# MT7601.net
KiCad netlist of a schematic drawn in Altium Designer
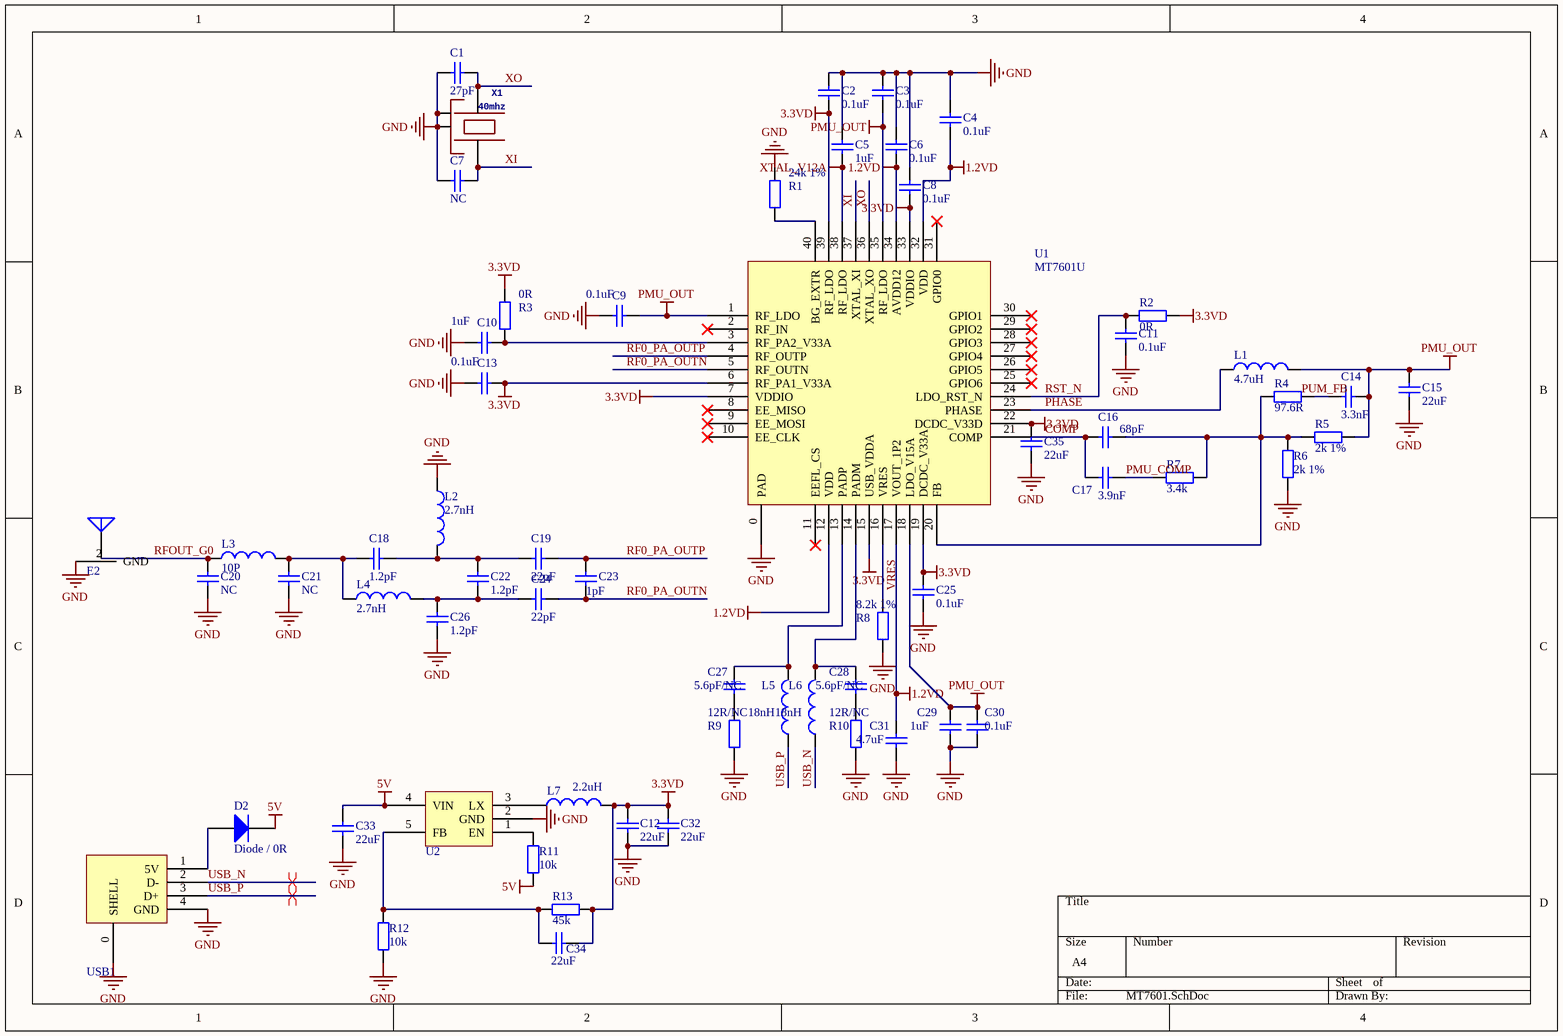
[diagram p0: MT7601.SchDoc]

(export (version "E")
  (design (tool "Eeschema 10.0.6"))
  (components
    (comp (ref "C1")
      (value "27pF")
      (footprint "0402")
      (description "Capacitor")
      (fields (field (name "PUBLISHER") "Altium Limited"))
      (libsource (lib "RTC6705") (part "Cap"))
    )
    (comp (ref "C2")
      (value "0.1uF")
      (footprint "0402")
      (description "Capacitor")
      (fields (field (name "PUBLISHER") "Altium Limited"))
      (libsource (lib "RTC6705") (part "Cap"))
    )
    (comp (ref "C3")
      (value "0.1uF")
      (footprint "0402")
      (description "Capacitor")
      (fields (field (name "PUBLISHER") "Altium Limited"))
      (libsource (lib "RTC6705") (part "Cap"))
    )
    (comp (ref "C4")
      (value "0.1uF")
      (footprint "0402")
      (description "Capacitor")
      (fields (field (name "PUBLISHER") "Altium Limited"))
      (libsource (lib "RTC6705") (part "Cap"))
    )
    (comp (ref "C5")
      (value "1uF")
      (footprint "0402")
      (description "Capacitor")
      (fields (field (name "PUBLISHER") "Altium Limited"))
      (libsource (lib "RTC6705") (part "Cap"))
    )
    (comp (ref "C6")
      (value "0.1uF")
      (footprint "0402")
      (description "Capacitor")
      (fields (field (name "PUBLISHER") "Altium Limited"))
      (libsource (lib "RTC6705") (part "Cap"))
    )
    (comp (ref "C7")
      (value "NC")
      (footprint "0402")
      (description "Capacitor")
      (fields (field (name "PUBLISHER") "Altium Limited"))
      (libsource (lib "RTC6705") (part "Cap"))
    )
    (comp (ref "C8")
      (value "0.1uF")
      (footprint "0402")
      (description "Capacitor")
      (fields (field (name "PUBLISHER") "Altium Limited"))
      (libsource (lib "RTC6705") (part "Cap"))
    )
    (comp (ref "C9")
      (value "0.1uF")
      (footprint "0402")
      (description "Capacitor")
      (fields (field (name "PUBLISHER") "Altium Limited"))
      (libsource (lib "RTC6705") (part "Cap"))
    )
    (comp (ref "C10")
      (value "1uF")
      (footprint "0402")
      (description "Capacitor")
      (fields (field (name "PUBLISHER") "Altium Limited"))
      (libsource (lib "RTC6705") (part "Cap"))
    )
    (comp (ref "C11")
      (value "0.1uF")
      (footprint "0402")
      (description "Capacitor")
      (fields (field (name "PUBLISHER") "Altium Limited"))
      (libsource (lib "RTC6705") (part "Cap"))
    )
    (comp (ref "C12")
      (value "22uF")
      (footprint "0805")
      (description "Capacitor")
      (fields (field (name "Comment") "Cap") (field (name "PUBLISHER") "Altium Limited"))
      (libsource (lib "RTC6705") (part "Cap"))
    )
    (comp (ref "C13")
      (value "0.1uF")
      (footprint "0402")
      (description "Capacitor")
      (fields (field (name "PUBLISHER") "Altium Limited"))
      (libsource (lib "RTC6705") (part "Cap"))
    )
    (comp (ref "C14")
      (value "3.3nF")
      (footprint "0402")
      (description "Capacitor")
      (fields (field (name "PUBLISHER") "Altium Limited"))
      (libsource (lib "RTC6705") (part "Cap"))
    )
    (comp (ref "C15")
      (value "22uF")
      (footprint "0805")
      (description "Capacitor")
      (fields (field (name "Comment") "Cap") (field (name "PUBLISHER") "Altium Limited"))
      (libsource (lib "RTC6705") (part "Cap"))
    )
    (comp (ref "C16")
      (value "68pF")
      (footprint "0402")
      (description "Capacitor")
      (fields (field (name "PUBLISHER") "Altium Limited"))
      (libsource (lib "RTC6705") (part "Cap"))
    )
    (comp (ref "C17")
      (value "3.9nF")
      (footprint "0402")
      (description "Capacitor")
      (fields (field (name "PUBLISHER") "Altium Limited"))
      (libsource (lib "RTC6705") (part "Cap"))
    )
    (comp (ref "C18")
      (value "1.2pF")
      (footprint "0402")
      (description "Capacitor")
      (fields (field (name "PUBLISHER") "Altium Limited"))
      (libsource (lib "RTC6705") (part "Cap"))
    )
    (comp (ref "C19")
      (value "22pF")
      (footprint "0402")
      (description "Capacitor")
      (fields (field (name "PUBLISHER") "Altium Limited"))
      (libsource (lib "RTC6705") (part "Cap"))
    )
    (comp (ref "C20")
      (value "NC")
      (footprint "0402")
      (description "Capacitor")
      (fields (field (name "PUBLISHER") "Altium Limited"))
      (libsource (lib "RTC6705") (part "Cap"))
    )
    (comp (ref "C21")
      (value "NC")
      (footprint "0402")
      (description "Capacitor")
      (fields (field (name "PUBLISHER") "Altium Limited"))
      (libsource (lib "RTC6705") (part "Cap"))
    )
    (comp (ref "C22")
      (value "1.2pF")
      (footprint "0402")
      (description "Capacitor")
      (fields (field (name "PUBLISHER") "Altium Limited"))
      (libsource (lib "RTC6705") (part "Cap"))
    )
    (comp (ref "C23")
      (value "1pF")
      (footprint "0402")
      (description "Capacitor")
      (fields (field (name "PUBLISHER") "Altium Limited"))
      (libsource (lib "RTC6705") (part "Cap"))
    )
    (comp (ref "C24")
      (value "22pF")
      (footprint "0402")
      (description "Capacitor")
      (fields (field (name "PUBLISHER") "Altium Limited"))
      (libsource (lib "RTC6705") (part "Cap"))
    )
    (comp (ref "C25")
      (value "0.1uF")
      (footprint "0402")
      (description "Capacitor")
      (fields (field (name "PUBLISHER") "Altium Limited"))
      (libsource (lib "RTC6705") (part "Cap"))
    )
    (comp (ref "C26")
      (value "1.2pF")
      (footprint "0402")
      (description "Capacitor")
      (fields (field (name "PUBLISHER") "Altium Limited"))
      (libsource (lib "RTC6705") (part "Cap"))
    )
    (comp (ref "C27")
      (value "5.6pF/NC")
      (footprint "0402")
      (description "Capacitor")
      (fields (field (name "PUBLISHER") "Altium Limited"))
      (libsource (lib "RTC6705") (part "Cap"))
    )
    (comp (ref "C28")
      (value "5.6pF/NC")
      (footprint "0402")
      (description "Capacitor")
      (fields (field (name "PUBLISHER") "Altium Limited"))
      (libsource (lib "RTC6705") (part "Cap"))
    )
    (comp (ref "C29")
      (value "1uF")
      (footprint "0402")
      (description "Capacitor")
      (fields (field (name "PUBLISHER") "Altium Limited"))
      (libsource (lib "RTC6705") (part "Cap"))
    )
    (comp (ref "C30")
      (value "0.1uF")
      (footprint "0402")
      (description "Capacitor")
      (fields (field (name "PUBLISHER") "Altium Limited"))
      (libsource (lib "RTC6705") (part "Cap"))
    )
    (comp (ref "C31")
      (value "4.7uF")
      (footprint "0603")
      (description "Capacitor")
      (fields (field (name "PUBLISHER") "Altium Limited"))
      (libsource (lib "RTC6705") (part "Cap"))
    )
    (comp (ref "C32")
      (value "22uF")
      (footprint "0805")
      (description "Capacitor")
      (fields (field (name "Comment") "Cap") (field (name "PUBLISHER") "Altium Limited"))
      (libsource (lib "RTC6705") (part "Cap"))
    )
    (comp (ref "C33")
      (value "22uF")
      (footprint "0805")
      (description "Capacitor")
      (fields (field (name "Comment") "Cap") (field (name "PUBLISHER") "Altium Limited"))
      (libsource (lib "RTC6705") (part "Cap"))
    )
    (comp (ref "C34")
      (value "22uF")
      (footprint "0402")
      (description "Capacitor")
      (fields (field (name "Comment") "Cap") (field (name "PUBLISHER") "Altium Limited"))
      (libsource (lib "RTC6705") (part "Cap"))
    )
    (comp (ref "C35")
      (value "22uF")
      (footprint "0805")
      (description "Capacitor")
      (fields (field (name "Comment") "Cap") (field (name "PUBLISHER") "Altium Limited"))
      (libsource (lib "RTC6705") (part "Cap"))
    )
    (comp (ref "D2")
      (value "Diode / 0R")
      (footprint "0805")
      (description "Default Diode")
      (fields (field (name "PUBLISHER") "Altium Limited"))
      (libsource (lib "Miscellaneous Devices") (part "Diode"))
    )
    (comp (ref "E2")
      (value "Antenna")
      (footprint "IPEX")
      (description "Generic Antenna")
      (fields (field (name "PUBLISHER") "Altium Limited"))
      (libsource (lib "Miscellaneous Devices") (part "Antenna"))
    )
    (comp (ref "L1")
      (value "4.7uH")
      (footprint "0805")
      (description "Inductor")
      (fields (field (name "PUBLISHER") "Altium Limited"))
      (libsource (lib "Miscellaneous Devices") (part "Inductor"))
    )
    (comp (ref "L2")
      (value "2.7nH")
      (footprint "0402")
      (description "Inductor")
      (fields (field (name "PUBLISHER") "Altium Limited"))
      (libsource (lib "Miscellaneous Devices") (part "Inductor"))
    )
    (comp (ref "L3")
      (value "10P")
      (footprint "0402")
      (description "Inductor")
      (fields (field (name "PUBLISHER") "Altium Limited"))
      (libsource (lib "Miscellaneous Devices") (part "Inductor"))
    )
    (comp (ref "L4")
      (value "2.7nH")
      (footprint "0402")
      (description "Inductor")
      (fields (field (name "PUBLISHER") "Altium Limited"))
      (libsource (lib "Miscellaneous Devices") (part "Inductor"))
    )
    (comp (ref "L5")
      (value "18nH")
      (footprint "0402")
      (description "Inductor")
      (fields (field (name "PUBLISHER") "Altium Limited"))
      (libsource (lib "Miscellaneous Devices") (part "Inductor"))
    )
    (comp (ref "L6")
      (value "18nH")
      (footprint "0402")
      (description "Inductor")
      (fields (field (name "PUBLISHER") "Altium Limited"))
      (libsource (lib "Miscellaneous Devices") (part "Inductor"))
    )
    (comp (ref "L7")
      (value "2.2uH")
      (footprint "0805")
      (description "Inductor")
      (fields (field (name "PUBLISHER") "Altium Limited"))
      (libsource (lib "Miscellaneous Devices") (part "Inductor"))
    )
    (comp (ref "R1")
      (value "24k 1%")
      (footprint "0402")
      (description "Resistor")
      (fields (field (name "PUBLISHER") "Altium Limited"))
      (libsource (lib "RTC6705") (part "Res2"))
    )
    (comp (ref "R2")
      (value "0R")
      (footprint "0402")
      (description "Resistor")
      (fields (field (name "PUBLISHER") "Altium Limited"))
      (libsource (lib "") (part "Res2_2"))
    )
    (comp (ref "R3")
      (value "0R")
      (footprint "0402")
      (description "Resistor")
      (fields (field (name "PUBLISHER") "Altium Limited"))
      (libsource (lib "RTC6705") (part "Res2"))
    )
    (comp (ref "R4")
      (value "97.6R")
      (footprint "0402")
      (description "Resistor")
      (fields (field (name "PUBLISHER") "Altium Limited"))
      (libsource (lib "") (part "Res2_2"))
    )
    (comp (ref "R5")
      (value "2k 1%")
      (footprint "0402")
      (description "Resistor")
      (fields (field (name "PUBLISHER") "Altium Limited"))
      (libsource (lib "") (part "Res2_2"))
    )
    (comp (ref "R6")
      (value "2k 1%")
      (footprint "0402")
      (description "Resistor")
      (fields (field (name "PUBLISHER") "Altium Limited"))
      (libsource (lib "") (part "Res2_1"))
    )
    (comp (ref "R7")
      (value "3.4k")
      (footprint "0402")
      (description "Resistor")
      (fields (field (name "PUBLISHER") "Altium Limited"))
      (libsource (lib "") (part "Res2_2"))
    )
    (comp (ref "R8")
      (value "8.2k 1%")
      (footprint "0402")
      (description "Resistor")
      (fields (field (name "PUBLISHER") "Altium Limited"))
      (libsource (lib "RTC6705") (part "Res2"))
    )
    (comp (ref "R9")
      (value "12R/NC")
      (footprint "0402")
      (description "Resistor")
      (fields (field (name "PUBLISHER") "Altium Limited"))
      (libsource (lib "RTC6705") (part "Res2"))
    )
    (comp (ref "R10")
      (value "12R/NC")
      (footprint "0402")
      (description "Resistor")
      (fields (field (name "PUBLISHER") "Altium Limited"))
      (libsource (lib "RTC6705") (part "Res2"))
    )
    (comp (ref "R11")
      (value "10k")
      (footprint "0402")
      (description "Resistor")
      (fields (field (name "PUBLISHER") "Altium Limited"))
      (libsource (lib "") (part "Res2_1"))
    )
    (comp (ref "R12")
      (value "10k")
      (footprint "0402")
      (description "Resistor")
      (fields (field (name "PUBLISHER") "Altium Limited"))
      (libsource (lib "RTC6705") (part "Res2"))
    )
    (comp (ref "R13")
      (value "45k")
      (footprint "0402")
      (description "Resistor")
      (fields (field (name "PUBLISHER") "Altium Limited"))
      (libsource (lib "") (part "Res2_3"))
    )
    (comp (ref "U1") (value "MT7601U") (footprint "MT7601U") (libsource (lib "WifiGain") (part "MT7601U")))
    (comp (ref "U2") (value "RT8059") (footprint "SOT23-5") (libsource (lib "WifiGain") (part "RT8059")))
    (comp (ref "USB1") (value "USB-A") (footprint "USB-A-Male") (libsource (lib "WifiGain") (part "USB-A")))
    (comp (ref "X1")
      (value "40mhz")
      (footprint "OSCILLATOR-3.2X2.5")
      (description "Crystal Oscillator in 3.2x2.5 SMD")
      (libsource (lib "sch") (part "OSCILLATOR-3.2X2.5"))
    )
  )
  (nets
    (net (code "1") (name "/COMP") (class "Default")
      (node (ref "C16") (pin "2") (pinfunction "2_2") (pintype "passive"))
      (node (ref "C17") (pin "2") (pinfunction "2_2") (pintype "passive"))
      (node (ref "U1") (pin "21") (pinfunction "COMP_21") (pintype "passive"))
    )
    (net (code "2") (name "/PHASE") (class "Default")
      (node (ref "L1") (pin "1") (pinfunction "1_1") (pintype "passive"))
      (node (ref "U1") (pin "23") (pinfunction "PHASE_23") (pintype "passive"))
    )
    (net (code "3") (name "/PMU_COMP") (class "Default")
      (node (ref "C17") (pin "1") (pinfunction "1_1") (pintype "passive"))
      (node (ref "R7") (pin "2") (pinfunction "2_2") (pintype "passive"))
    )
    (net (code "5") (name "/RF0_PA_OUTN") (class "Default")
      (node (ref "C23") (pin "1") (pinfunction "1_1") (pintype "passive"))
      (node (ref "C24") (pin "2") (pinfunction "2_2") (pintype "passive"))
      (node (ref "U1") (pin "5") (pinfunction "RF_OUTN_5") (pintype "passive"))
    )
    (net (code "6") (name "/RF0_PA_OUTP") (class "Default")
      (node (ref "C19") (pin "2") (pinfunction "2_2") (pintype "passive"))
      (node (ref "C23") (pin "2") (pinfunction "2_2") (pintype "passive"))
      (node (ref "U1") (pin "4") (pinfunction "RF_OUTP_4") (pintype "passive"))
    )
    (net (code "7") (name "/RFOUT_G0") (class "Default")
      (node (ref "C20") (pin "2") (pinfunction "2_2") (pintype "passive"))
      (node (ref "E2") (pin "1") (pinfunction "ANT_1") (pintype "passive"))
      (node (ref "L3") (pin "1") (pinfunction "1_1") (pintype "passive"))
    )
    (net (code "8") (name "/RST_N") (class "Default")
      (node (ref "C11") (pin "1") (pinfunction "1_1") (pintype "passive"))
      (node (ref "R2") (pin "2") (pinfunction "2_2") (pintype "passive"))
      (node (ref "U1") (pin "24") (pinfunction "LDO_RST_N_24") (pintype "passive"))
    )
    (net (code "9") (name "/USB_N") (class "Default")
      (node (ref "L6") (pin "1") (pinfunction "1_1") (pintype "passive"))
      (node (ref "USB1") (pin "2") (pinfunction "D-_2") (pintype "passive"))
    )
    (net (code "10") (name "/USB_P") (class "Default")
      (node (ref "L5") (pin "1") (pinfunction "1_1") (pintype "passive"))
      (node (ref "USB1") (pin "3") (pinfunction "D+_3") (pintype "passive"))
    )
    (net (code "11") (name "/VRES") (class "Default")
      (node (ref "R8") (pin "2") (pinfunction "2_2") (pintype "passive"))
      (node (ref "U1") (pin "16") (pinfunction "VRES_16") (pintype "passive"))
    )
    (net (code "12") (name "/XI") (class "Default")
      (node (ref "C7") (pin "2") (pinfunction "2_2") (pintype "passive"))
      (node (ref "U1") (pin "37") (pinfunction "XTAL_XI_37") (pintype "passive"))
      (node (ref "X1") (pin "3") (pinfunction "3_3") (pintype "passive"))
    )
    (net (code "13") (name "/XO") (class "Default")
      (node (ref "C1") (pin "2") (pinfunction "2_2") (pintype "passive"))
      (node (ref "U1") (pin "36") (pinfunction "XTAL_XO_36") (pintype "passive"))
      (node (ref "X1") (pin "1") (pinfunction "1_1") (pintype "passive"))
    )
    (net (code "14") (name "1.2VD") (class "Default")
      (node (ref "C31") (pin "1") (pinfunction "1_1") (pintype "passive"))
      (node (ref "C4") (pin "2") (pinfunction "2_2") (pintype "passive"))
      (node (ref "C6") (pin "2") (pinfunction "2_2") (pintype "passive"))
      (node (ref "U1") (pin "12") (pinfunction "VDD_12") (pintype "passive"))
      (node (ref "U1") (pin "17") (pinfunction "VOUT_1P2_17") (pintype "passive"))
      (node (ref "U1") (pin "32") (pinfunction "VDD_32") (pintype "passive"))
      (node (ref "U1") (pin "34") (pinfunction "AVDD12_34") (pintype "passive"))
    )
    (net (code "15") (name "3.3VD") (class "Default")
      (node (ref "C12") (pin "2") (pinfunction "2_2") (pintype "passive"))
      (node (ref "C13") (pin "1") (pinfunction "1_1") (pintype "passive"))
      (node (ref "C2") (pin "2") (pinfunction "2_2") (pintype "passive"))
      (node (ref "C25") (pin "2") (pinfunction "2_2") (pintype "passive"))
      (node (ref "C32") (pin "2") (pinfunction "2_2") (pintype "passive"))
      (node (ref "C34") (pin "1") (pinfunction "1_1") (pintype "passive"))
      (node (ref "C35") (pin "2") (pinfunction "2_2") (pintype "passive"))
      (node (ref "C8") (pin "2") (pinfunction "2_2") (pintype "passive"))
      (node (ref "L7") (pin "2") (pinfunction "2_2") (pintype "passive"))
      (node (ref "R13") (pin "2") (pinfunction "2_2") (pintype "passive"))
      (node (ref "R2") (pin "1") (pinfunction "1_1") (pintype "passive"))
      (node (ref "R3") (pin "2") (pinfunction "2_2") (pintype "passive"))
      (node (ref "U1") (pin "15") (pinfunction "USB_VDDA_15") (pintype "passive"))
      (node (ref "U1") (pin "19") (pinfunction "DCDC_V33A_19") (pintype "passive"))
      (node (ref "U1") (pin "22") (pinfunction "DCDC_V33D_22") (pintype "passive"))
      (node (ref "U1") (pin "33") (pinfunction "VDDIO_33") (pintype "passive"))
      (node (ref "U1") (pin "39") (pinfunction "RF_LDO_39") (pintype "passive"))
      (node (ref "U1") (pin "6") (pinfunction "RF_PA1_V33A_6") (pintype "passive"))
      (node (ref "U1") (pin "7") (pinfunction "VDDIO_7") (pintype "passive"))
    )
    (net (code "16") (name "5V") (class "Default")
      (node (ref "C33") (pin "2") (pinfunction "2_2") (pintype "passive"))
      (node (ref "D2") (pin "2") (pinfunction "K_2") (pintype "passive"))
      (node (ref "R11") (pin "2") (pinfunction "2_2") (pintype "passive"))
      (node (ref "U2") (pin "4") (pinfunction "VIN_4") (pintype "passive"))
    )
    (net (code "17") (name "GND") (class "Default")
      (node (ref "C1") (pin "1") (pinfunction "1_1") (pintype "passive"))
      (node (ref "C10") (pin "2") (pinfunction "2_2") (pintype "passive"))
      (node (ref "C11") (pin "2") (pinfunction "2_2") (pintype "passive"))
      (node (ref "C12") (pin "1") (pinfunction "1_1") (pintype "passive"))
      (node (ref "C13") (pin "2") (pinfunction "2_2") (pintype "passive"))
      (node (ref "C15") (pin "1") (pinfunction "1_1") (pintype "passive"))
      (node (ref "C2") (pin "1") (pinfunction "1_1") (pintype "passive"))
      (node (ref "C20") (pin "1") (pinfunction "1_1") (pintype "passive"))
      (node (ref "C21") (pin "1") (pinfunction "1_1") (pintype "passive"))
      (node (ref "C25") (pin "1") (pinfunction "1_1") (pintype "passive"))
      (node (ref "C26") (pin "2") (pinfunction "2_2") (pintype "passive"))
      (node (ref "C29") (pin "2") (pinfunction "2_2") (pintype "passive"))
      (node (ref "C3") (pin "1") (pinfunction "1_1") (pintype "passive"))
      (node (ref "C30") (pin "2") (pinfunction "2_2") (pintype "passive"))
      (node (ref "C31") (pin "2") (pinfunction "2_2") (pintype "passive"))
      (node (ref "C32") (pin "1") (pinfunction "1_1") (pintype "passive"))
      (node (ref "C33") (pin "1") (pinfunction "1_1") (pintype "passive"))
      (node (ref "C35") (pin "1") (pinfunction "1_1") (pintype "passive"))
      (node (ref "C4") (pin "1") (pinfunction "1_1") (pintype "passive"))
      (node (ref "C5") (pin "1") (pinfunction "1_1") (pintype "passive"))
      (node (ref "C6") (pin "1") (pinfunction "1_1") (pintype "passive"))
      (node (ref "C7") (pin "1") (pinfunction "1_1") (pintype "passive"))
      (node (ref "C8") (pin "1") (pinfunction "1_1") (pintype "passive"))
      (node (ref "C9") (pin "2") (pinfunction "2_2") (pintype "passive"))
      (node (ref "E2") (pin "2") (pinfunction "GND_2") (pintype "passive"))
      (node (ref "L2") (pin "1") (pinfunction "1_1") (pintype "passive"))
      (node (ref "R1") (pin "2") (pinfunction "2_2") (pintype "passive"))
      (node (ref "R10") (pin "1") (pinfunction "1_1") (pintype "passive"))
      (node (ref "R12") (pin "1") (pinfunction "1_1") (pintype "passive"))
      (node (ref "R6") (pin "2") (pinfunction "2_2") (pintype "passive"))
      (node (ref "R8") (pin "1") (pinfunction "1_1") (pintype "passive"))
      (node (ref "R9") (pin "1") (pinfunction "1_1") (pintype "passive"))
      (node (ref "U1") (pin "0") (pinfunction "PAD_0") (pintype "passive"))
      (node (ref "U2") (pin "2") (pinfunction "GND_2") (pintype "passive"))
      (node (ref "USB1") (pin "0") (pinfunction "SHELL_0") (pintype "passive"))
      (node (ref "USB1") (pin "4") (pinfunction "GND_4") (pintype "passive"))
      (node (ref "X1") (pin "2") (pinfunction "NC_2_2") (pintype "open_emitter"))
      (node (ref "X1") (pin "4") (pinfunction "NC_4_4") (pintype "open_emitter"))
    )
    (net (code "18") (name "Net-(C14-Pad2)") (class "Default")
      (node (ref "C14") (pin "2") (pinfunction "2_2") (pintype "passive"))
      (node (ref "R4") (pin "1") (pinfunction "1_1") (pintype "passive"))
    )
    (net (code "19") (name "Net-(C18-Pad1)") (class "Default")
      (node (ref "C18") (pin "1") (pinfunction "1_1") (pintype "passive"))
      (node (ref "C19") (pin "1") (pinfunction "1_1") (pintype "passive"))
      (node (ref "C22") (pin "1") (pinfunction "1_1") (pintype "passive"))
      (node (ref "L2") (pin "2") (pinfunction "2_2") (pintype "passive"))
    )
    (net (code "20") (name "Net-(C18-Pad2)") (class "Default")
      (node (ref "C18") (pin "2") (pinfunction "2_2") (pintype "passive"))
      (node (ref "C21") (pin "2") (pinfunction "2_2") (pintype "passive"))
      (node (ref "L3") (pin "2") (pinfunction "2_2") (pintype "passive"))
      (node (ref "L4") (pin "1") (pinfunction "1_1") (pintype "passive"))
    )
    (net (code "21") (name "Net-(C22-Pad2)") (class "Default")
      (node (ref "C22") (pin "2") (pinfunction "2_2") (pintype "passive"))
      (node (ref "C24") (pin "1") (pinfunction "1_1") (pintype "passive"))
      (node (ref "C26") (pin "1") (pinfunction "1_1") (pintype "passive"))
      (node (ref "L4") (pin "2") (pinfunction "2_2") (pintype "passive"))
    )
    (net (code "22") (name "Net-(C27-Pad2)") (class "Default")
      (node (ref "C27") (pin "2") (pinfunction "2_2") (pintype "passive"))
      (node (ref "R9") (pin "2") (pinfunction "2_2") (pintype "passive"))
    )
    (net (code "23") (name "Net-(C28-Pad2)") (class "Default")
      (node (ref "C28") (pin "2") (pinfunction "2_2") (pintype "passive"))
      (node (ref "R10") (pin "2") (pinfunction "2_2") (pintype "passive"))
    )
    (net (code "24") (name "Net-(D2-A)") (class "Default")
      (node (ref "D2") (pin "1") (pinfunction "A_1") (pintype "passive"))
      (node (ref "USB1") (pin "1") (pinfunction "5V_1") (pintype "passive"))
    )
    (net (code "25") (name "Net-(U1-BG_EXTR)") (class "Default")
      (node (ref "R1") (pin "1") (pinfunction "1_1") (pintype "passive"))
      (node (ref "U1") (pin "40") (pinfunction "BG_EXTR_40") (pintype "passive"))
    )
    (net (code "26") (name "Net-(U1-FB)") (class "Default")
      (node (ref "C16") (pin "1") (pinfunction "1_1") (pintype "passive"))
      (node (ref "R4") (pin "2") (pinfunction "2_2") (pintype "passive"))
      (node (ref "R5") (pin "2") (pinfunction "2_2") (pintype "passive"))
      (node (ref "R6") (pin "1") (pinfunction "1_1") (pintype "passive"))
      (node (ref "R7") (pin "1") (pinfunction "1_1") (pintype "passive"))
      (node (ref "U1") (pin "20") (pinfunction "FB_20") (pintype "passive"))
    )
    (net (code "27") (name "Net-(U1-PADM)") (class "Default")
      (node (ref "C28") (pin "1") (pinfunction "1_1") (pintype "passive"))
      (node (ref "L6") (pin "2") (pinfunction "2_2") (pintype "passive"))
      (node (ref "U1") (pin "14") (pinfunction "PADM_14") (pintype "passive"))
    )
    (net (code "28") (name "Net-(U1-PADP)") (class "Default")
      (node (ref "C27") (pin "1") (pinfunction "1_1") (pintype "passive"))
      (node (ref "L5") (pin "2") (pinfunction "2_2") (pintype "passive"))
      (node (ref "U1") (pin "13") (pinfunction "PADP_13") (pintype "passive"))
    )
    (net (code "29") (name "Net-(U1-RF_PA2_V33A)") (class "Default")
      (node (ref "C10") (pin "1") (pinfunction "1_1") (pintype "passive"))
      (node (ref "R3") (pin "1") (pinfunction "1_1") (pintype "passive"))
      (node (ref "U1") (pin "3") (pinfunction "RF_PA2_V33A_3") (pintype "passive"))
    )
    (net (code "30") (name "Net-(U2-EN)") (class "Default")
      (node (ref "R11") (pin "1") (pinfunction "1_1") (pintype "passive"))
      (node (ref "U2") (pin "1") (pinfunction "EN_1") (pintype "passive"))
    )
    (net (code "31") (name "Net-(U2-FB)") (class "Default")
      (node (ref "C34") (pin "2") (pinfunction "2_2") (pintype "passive"))
      (node (ref "R12") (pin "2") (pinfunction "2_2") (pintype "passive"))
      (node (ref "R13") (pin "1") (pinfunction "1_1") (pintype "passive"))
      (node (ref "U2") (pin "5") (pinfunction "FB_5") (pintype "passive"))
    )
    (net (code "32") (name "Net-(U2-LX)") (class "Default")
      (node (ref "L7") (pin "1") (pinfunction "1_1") (pintype "passive"))
      (node (ref "U2") (pin "3") (pinfunction "LX_3") (pintype "passive"))
    )
    (net (code "33") (name "PMU_OUT") (class "Default")
      (node (ref "C14") (pin "1") (pinfunction "1_1") (pintype "passive"))
      (node (ref "C15") (pin "2") (pinfunction "2_2") (pintype "passive"))
      (node (ref "C29") (pin "1") (pinfunction "1_1") (pintype "passive"))
      (node (ref "C3") (pin "2") (pinfunction "2_2") (pintype "passive"))
      (node (ref "C30") (pin "1") (pinfunction "1_1") (pintype "passive"))
      (node (ref "C9") (pin "1") (pinfunction "1_1") (pintype "passive"))
      (node (ref "L1") (pin "2") (pinfunction "2_2") (pintype "passive"))
      (node (ref "R5") (pin "1") (pinfunction "1_1") (pintype "passive"))
      (node (ref "U1") (pin "1") (pinfunction "RF_LDO_1") (pintype "passive"))
      (node (ref "U1") (pin "18") (pinfunction "LDO_V15A_18") (pintype "passive"))
      (node (ref "U1") (pin "35") (pinfunction "RF_LDO_35") (pintype "passive"))
    )
    (net (code "34") (name "XTAL_V12A") (class "Default")
      (node (ref "C5") (pin "2") (pinfunction "2_2") (pintype "passive"))
      (node (ref "U1") (pin "38") (pinfunction "RF_LDO_38") (pintype "passive"))
    )
    (net (code "35") (name "unconnected-(U1-EEFL_CS-Pad11)") (class "Default")
      (node (ref "U1") (pin "11") (pinfunction "EEFL_CS_11") (pintype "passive+no_connect"))
    )
    (net (code "36") (name "unconnected-(U1-EE_CLK-Pad10)") (class "Default")
      (node (ref "U1") (pin "10") (pinfunction "EE_CLK_10") (pintype "passive+no_connect"))
    )
    (net (code "37") (name "unconnected-(U1-EE_MISO-Pad8)") (class "Default")
      (node (ref "U1") (pin "8") (pinfunction "EE_MISO_8") (pintype "passive+no_connect"))
    )
    (net (code "38") (name "unconnected-(U1-EE_MOSI-Pad9)") (class "Default")
      (node (ref "U1") (pin "9") (pinfunction "EE_MOSI_9") (pintype "passive+no_connect"))
    )
    (net (code "39") (name "unconnected-(U1-GPIO0-Pad31)") (class "Default")
      (node (ref "U1") (pin "31") (pinfunction "GPIO0_31") (pintype "passive+no_connect"))
    )
    (net (code "40") (name "unconnected-(U1-GPIO1-Pad30)") (class "Default")
      (node (ref "U1") (pin "30") (pinfunction "GPIO1_30") (pintype "passive+no_connect"))
    )
    (net (code "41") (name "unconnected-(U1-GPIO2-Pad29)") (class "Default")
      (node (ref "U1") (pin "29") (pinfunction "GPIO2_29") (pintype "passive+no_connect"))
    )
    (net (code "42") (name "unconnected-(U1-GPIO3-Pad28)") (class "Default")
      (node (ref "U1") (pin "28") (pinfunction "GPIO3_28") (pintype "passive+no_connect"))
    )
    (net (code "43") (name "unconnected-(U1-GPIO4-Pad27)") (class "Default")
      (node (ref "U1") (pin "27") (pinfunction "GPIO4_27") (pintype "passive+no_connect"))
    )
    (net (code "44") (name "unconnected-(U1-GPIO5-Pad26)") (class "Default")
      (node (ref "U1") (pin "26") (pinfunction "GPIO5_26") (pintype "passive+no_connect"))
    )
    (net (code "45") (name "unconnected-(U1-GPIO6-Pad25)") (class "Default")
      (node (ref "U1") (pin "25") (pinfunction "GPIO6_25") (pintype "passive+no_connect"))
    )
    (net (code "46") (name "unconnected-(U1-RF_IN-Pad2)") (class "Default")
      (node (ref "U1") (pin "2") (pinfunction "RF_IN_2") (pintype "passive+no_connect"))
    )
  )
)
